# large_sense_pcb_d.net
KiCad netlist of a schematic drawn in EAGLE
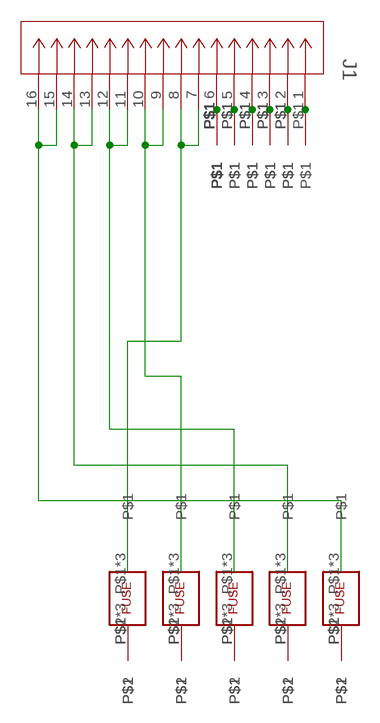
[diagram p0: schematic, sheet 1]

(export (version "E")
  (design (tool "Eeschema 10.0.6"))
  (components
    (comp (ref "J1")
      (value "DF11-16DP-2DSA(01)")
      (footprint "eagle-import:CONN_DF11-16DP-2DSA(01)_HIR")
      (fields (field (name "COPYRIGHT") "Copyright (C) 2023 Ultra Librarian. All rights reserved."))
      (libsource (lib "eagle-import") (part "DF11-16DP-2DSA(01)"))
    )
    (comp (ref "U$1")
      (value "FUSE")
      (footprint "eagle-import:FUSE_PADS")
      (libsource (lib "eagle-import") (part "FUSE"))
    )
    (comp (ref "U$2")
      (value "FUSE")
      (footprint "eagle-import:FUSE_PADS")
      (libsource (lib "eagle-import") (part "FUSE"))
    )
    (comp (ref "U$3")
      (value "FUSE")
      (footprint "eagle-import:FUSE_PADS")
      (libsource (lib "eagle-import") (part "FUSE"))
    )
    (comp (ref "U$4")
      (value "FUSE")
      (footprint "eagle-import:FUSE_PADS")
      (libsource (lib "eagle-import") (part "FUSE"))
    )
    (comp (ref "U$5")
      (value "FUSE")
      (footprint "eagle-import:FUSE_PADS")
      (libsource (lib "eagle-import") (part "FUSE"))
    )
    (comp (ref "U$6")
      (value "BB_CONTACT")
      (footprint "eagle-import:BB_CONTACT")
      (libsource (lib "eagle-import") (part "BB_CONTACT"))
    )
    (comp (ref "U$7")
      (value "BB_CONTACT")
      (footprint "eagle-import:BB_CONTACT")
      (libsource (lib "eagle-import") (part "BB_CONTACT"))
    )
    (comp (ref "U$8")
      (value "BB_CONTACT")
      (footprint "eagle-import:BB_CONTACT")
      (libsource (lib "eagle-import") (part "BB_CONTACT"))
    )
    (comp (ref "U$9")
      (value "BB_CONTACT")
      (footprint "eagle-import:BB_CONTACT")
      (libsource (lib "eagle-import") (part "BB_CONTACT"))
    )
    (comp (ref "U$10")
      (value "BB_CONTACT")
      (footprint "eagle-import:BB_CONTACT")
      (libsource (lib "eagle-import") (part "BB_CONTACT"))
    )
    (comp (ref "U$12")
      (value "THERM_PIN")
      (footprint "eagle-import:THERM_PIN")
      (libsource (lib "eagle-import") (part "THERM_PIN"))
    )
    (comp (ref "U$13")
      (value "THERM_PIN")
      (footprint "eagle-import:THERM_PIN")
      (libsource (lib "eagle-import") (part "THERM_PIN"))
    )
    (comp (ref "U$14")
      (value "THERM_PIN")
      (footprint "eagle-import:THERM_PIN")
      (libsource (lib "eagle-import") (part "THERM_PIN"))
    )
    (comp (ref "U$15")
      (value "THERM_PIN")
      (footprint "eagle-import:THERM_PIN")
      (libsource (lib "eagle-import") (part "THERM_PIN"))
    )
    (comp (ref "U$16")
      (value "THERM_PIN")
      (footprint "eagle-import:THERM_PIN")
      (libsource (lib "eagle-import") (part "THERM_PIN"))
    )
    (comp (ref "U$17")
      (value "THERM_PIN")
      (footprint "eagle-import:THERM_PIN")
      (libsource (lib "eagle-import") (part "THERM_PIN"))
    )
    (comp (ref "U$18")
      (value "THERM_PIN")
      (footprint "eagle-import:THERM_PIN")
      (libsource (lib "eagle-import") (part "THERM_PIN"))
    )
    (comp (ref "U$19")
      (value "THERM_PIN")
      (footprint "eagle-import:THERM_PIN")
      (libsource (lib "eagle-import") (part "THERM_PIN"))
    )
    (comp (ref "U$20")
      (value "THERM_PIN")
      (footprint "eagle-import:THERM_PIN")
      (libsource (lib "eagle-import") (part "THERM_PIN"))
    )
    (comp (ref "U$22")
      (value "THERM_PIN")
      (footprint "eagle-import:THERM_PIN")
      (libsource (lib "eagle-import") (part "THERM_PIN"))
    )
    (comp (ref "U$23")
      (value "THERM_PIN")
      (footprint "eagle-import:THERM_PIN")
      (libsource (lib "eagle-import") (part "THERM_PIN"))
    )
    (comp (ref "U$24")
      (value "THERM_PIN")
      (footprint "eagle-import:THERM_PIN")
      (libsource (lib "eagle-import") (part "THERM_PIN"))
    )
    (comp (ref "U$25")
      (value "THERM_PIN")
      (footprint "eagle-import:THERM_PIN")
      (libsource (lib "eagle-import") (part "THERM_PIN"))
    )
    (comp (ref "U$26")
      (value "THERM_PIN")
      (footprint "eagle-import:THERM_PIN")
      (libsource (lib "eagle-import") (part "THERM_PIN"))
    )
    (comp (ref "U$27")
      (value "THERM_PIN")
      (footprint "eagle-import:THERM_PIN")
      (libsource (lib "eagle-import") (part "THERM_PIN"))
    )
    (comp (ref "U$28")
      (value "THERM_PIN")
      (footprint "eagle-import:THERM_PIN")
      (libsource (lib "eagle-import") (part "THERM_PIN"))
    )
    (comp (ref "U$29")
      (value "THERM_PIN")
      (footprint "eagle-import:THERM_PIN")
      (libsource (lib "eagle-import") (part "THERM_PIN"))
    )
    (comp (ref "U$30")
      (value "THERM_PIN")
      (footprint "eagle-import:THERM_PIN")
      (libsource (lib "eagle-import") (part "THERM_PIN"))
    )
  )
  (nets
    (net (code "1") (name "Net-(J1-Pad1)") (class "Default")
      (node (ref "J1") (pin "1") (pinfunction "1_1") (pintype "passive"))
      (node (ref "U$30") (pin "P$1") (pinfunction "P$1_P$1") (pintype "bidirectional"))
    )
    (net (code "2") (name "Net-(J1-Pad2)") (class "Default")
      (node (ref "J1") (pin "2") (pinfunction "2_2") (pintype "passive"))
      (node (ref "U$28") (pin "P$1") (pinfunction "P$1_P$1") (pintype "bidirectional"))
      (node (ref "U$29") (pin "P$1") (pinfunction "P$1_P$1") (pintype "bidirectional"))
    )
    (net (code "3") (name "Net-(J1-Pad3)") (class "Default")
      (node (ref "J1") (pin "3") (pinfunction "3_3") (pintype "passive"))
      (node (ref "U$26") (pin "P$1") (pinfunction "P$1_P$1") (pintype "bidirectional"))
      (node (ref "U$27") (pin "P$1") (pinfunction "P$1_P$1") (pintype "bidirectional"))
    )
    (net (code "4") (name "Net-(J1-Pad4)") (class "Default")
      (node (ref "J1") (pin "4") (pinfunction "4_4") (pintype "passive"))
      (node (ref "U$24") (pin "P$1") (pinfunction "P$1_P$1") (pintype "bidirectional"))
      (node (ref "U$25") (pin "P$1") (pinfunction "P$1_P$1") (pintype "bidirectional"))
    )
    (net (code "5") (name "Net-(J1-Pad5)") (class "Default")
      (node (ref "J1") (pin "5") (pinfunction "5_5") (pintype "passive"))
      (node (ref "U$22") (pin "P$1") (pinfunction "P$1_P$1") (pintype "bidirectional"))
      (node (ref "U$23") (pin "P$1") (pinfunction "P$1_P$1") (pintype "bidirectional"))
    )
    (net (code "6") (name "Net-(J1-Pad6)") (class "Default")
      (node (ref "J1") (pin "6") (pinfunction "6_6") (pintype "passive"))
      (node (ref "U$12") (pin "P$1") (pinfunction "P$1_P$1") (pintype "bidirectional"))
      (node (ref "U$13") (pin "P$1") (pinfunction "P$1_P$1") (pintype "bidirectional"))
      (node (ref "U$14") (pin "P$1") (pinfunction "P$1_P$1") (pintype "bidirectional"))
      (node (ref "U$15") (pin "P$1") (pinfunction "P$1_P$1") (pintype "bidirectional"))
      (node (ref "U$16") (pin "P$1") (pinfunction "P$1_P$1") (pintype "bidirectional"))
      (node (ref "U$17") (pin "P$1") (pinfunction "P$1_P$1") (pintype "bidirectional"))
      (node (ref "U$18") (pin "P$1") (pinfunction "P$1_P$1") (pintype "bidirectional"))
      (node (ref "U$19") (pin "P$1") (pinfunction "P$1_P$1") (pintype "bidirectional"))
      (node (ref "U$20") (pin "P$1") (pinfunction "P$1_P$1") (pintype "bidirectional"))
    )
    (net (code "7") (name "Net-(J1-Pad7)") (class "Default")
      (node (ref "J1") (pin "7") (pinfunction "7_7") (pintype "passive"))
      (node (ref "J1") (pin "8") (pinfunction "8_8") (pintype "passive"))
      (node (ref "U$1") (pin "P$1") (pinfunction "P$1_P$1") (pintype "bidirectional"))
      (node (ref "U$1") (pin "P$3") (pinfunction "P$1_P$3") (pintype "bidirectional"))
      (node (ref "U$1") (pin "P$5") (pinfunction "P$1_P$5") (pintype "bidirectional"))
    )
    (net (code "8") (name "Net-(J1-Pad10)") (class "Default")
      (node (ref "J1") (pin "10") (pinfunction "10_10") (pintype "passive"))
      (node (ref "J1") (pin "9") (pinfunction "9_9") (pintype "passive"))
      (node (ref "U$2") (pin "P$1") (pinfunction "P$1_P$1") (pintype "bidirectional"))
      (node (ref "U$2") (pin "P$3") (pinfunction "P$1_P$3") (pintype "bidirectional"))
      (node (ref "U$2") (pin "P$5") (pinfunction "P$1_P$5") (pintype "bidirectional"))
    )
    (net (code "9") (name "Net-(J1-Pad11)") (class "Default")
      (node (ref "J1") (pin "11") (pinfunction "11_11") (pintype "passive"))
      (node (ref "J1") (pin "12") (pinfunction "12_12") (pintype "passive"))
      (node (ref "U$3") (pin "P$1") (pinfunction "P$1_P$1") (pintype "bidirectional"))
      (node (ref "U$3") (pin "P$3") (pinfunction "P$1_P$3") (pintype "bidirectional"))
      (node (ref "U$3") (pin "P$5") (pinfunction "P$1_P$5") (pintype "bidirectional"))
    )
    (net (code "10") (name "Net-(J1-Pad13)") (class "Default")
      (node (ref "J1") (pin "13") (pinfunction "13_13") (pintype "passive"))
      (node (ref "J1") (pin "14") (pinfunction "14_14") (pintype "passive"))
      (node (ref "U$4") (pin "P$1") (pinfunction "P$1_P$1") (pintype "bidirectional"))
      (node (ref "U$4") (pin "P$3") (pinfunction "P$1_P$3") (pintype "bidirectional"))
      (node (ref "U$4") (pin "P$5") (pinfunction "P$1_P$5") (pintype "bidirectional"))
    )
    (net (code "11") (name "Net-(J1-Pad15)") (class "Default")
      (node (ref "J1") (pin "15") (pinfunction "15_15") (pintype "passive"))
      (node (ref "J1") (pin "16") (pinfunction "16_16") (pintype "passive"))
      (node (ref "U$5") (pin "P$1") (pinfunction "P$1_P$1") (pintype "bidirectional"))
      (node (ref "U$5") (pin "P$3") (pinfunction "P$1_P$3") (pintype "bidirectional"))
      (node (ref "U$5") (pin "P$5") (pinfunction "P$1_P$5") (pintype "bidirectional"))
    )
    (net (code "12") (name "Net-(U$1-P$2-PadP$4)") (class "Default")
      (node (ref "U$1") (pin "P$2") (pinfunction "P$2_P$2") (pintype "bidirectional"))
      (node (ref "U$1") (pin "P$4") (pinfunction "P$2_P$4") (pintype "bidirectional"))
      (node (ref "U$1") (pin "P$6") (pinfunction "P$2_P$6") (pintype "bidirectional"))
      (node (ref "U$6") (pin "P$1") (pinfunction "P$1_P$1") (pintype "bidirectional"))
    )
    (net (code "13") (name "Net-(U$2-P$2-PadP$4)") (class "Default")
      (node (ref "U$2") (pin "P$2") (pinfunction "P$2_P$2") (pintype "bidirectional"))
      (node (ref "U$2") (pin "P$4") (pinfunction "P$2_P$4") (pintype "bidirectional"))
      (node (ref "U$2") (pin "P$6") (pinfunction "P$2_P$6") (pintype "bidirectional"))
      (node (ref "U$7") (pin "P$1") (pinfunction "P$1_P$1") (pintype "bidirectional"))
    )
    (net (code "14") (name "Net-(U$3-P$2-PadP$4)") (class "Default")
      (node (ref "U$3") (pin "P$2") (pinfunction "P$2_P$2") (pintype "bidirectional"))
      (node (ref "U$3") (pin "P$4") (pinfunction "P$2_P$4") (pintype "bidirectional"))
      (node (ref "U$3") (pin "P$6") (pinfunction "P$2_P$6") (pintype "bidirectional"))
      (node (ref "U$8") (pin "P$1") (pinfunction "P$1_P$1") (pintype "bidirectional"))
    )
    (net (code "15") (name "Net-(U$4-P$2-PadP$4)") (class "Default")
      (node (ref "U$4") (pin "P$2") (pinfunction "P$2_P$2") (pintype "bidirectional"))
      (node (ref "U$4") (pin "P$4") (pinfunction "P$2_P$4") (pintype "bidirectional"))
      (node (ref "U$4") (pin "P$6") (pinfunction "P$2_P$6") (pintype "bidirectional"))
      (node (ref "U$9") (pin "P$1") (pinfunction "P$1_P$1") (pintype "bidirectional"))
    )
    (net (code "16") (name "Net-(U$10-PadP$1)") (class "Default")
      (node (ref "U$10") (pin "P$1") (pinfunction "P$1_P$1") (pintype "bidirectional"))
      (node (ref "U$5") (pin "P$2") (pinfunction "P$2_P$2") (pintype "bidirectional"))
      (node (ref "U$5") (pin "P$4") (pinfunction "P$2_P$4") (pintype "bidirectional"))
      (node (ref "U$5") (pin "P$6") (pinfunction "P$2_P$6") (pintype "bidirectional"))
    )
  )
)
